# Teensy_FrequencyShield.net
KiCad netlist of a schematic drawn in EAGLE
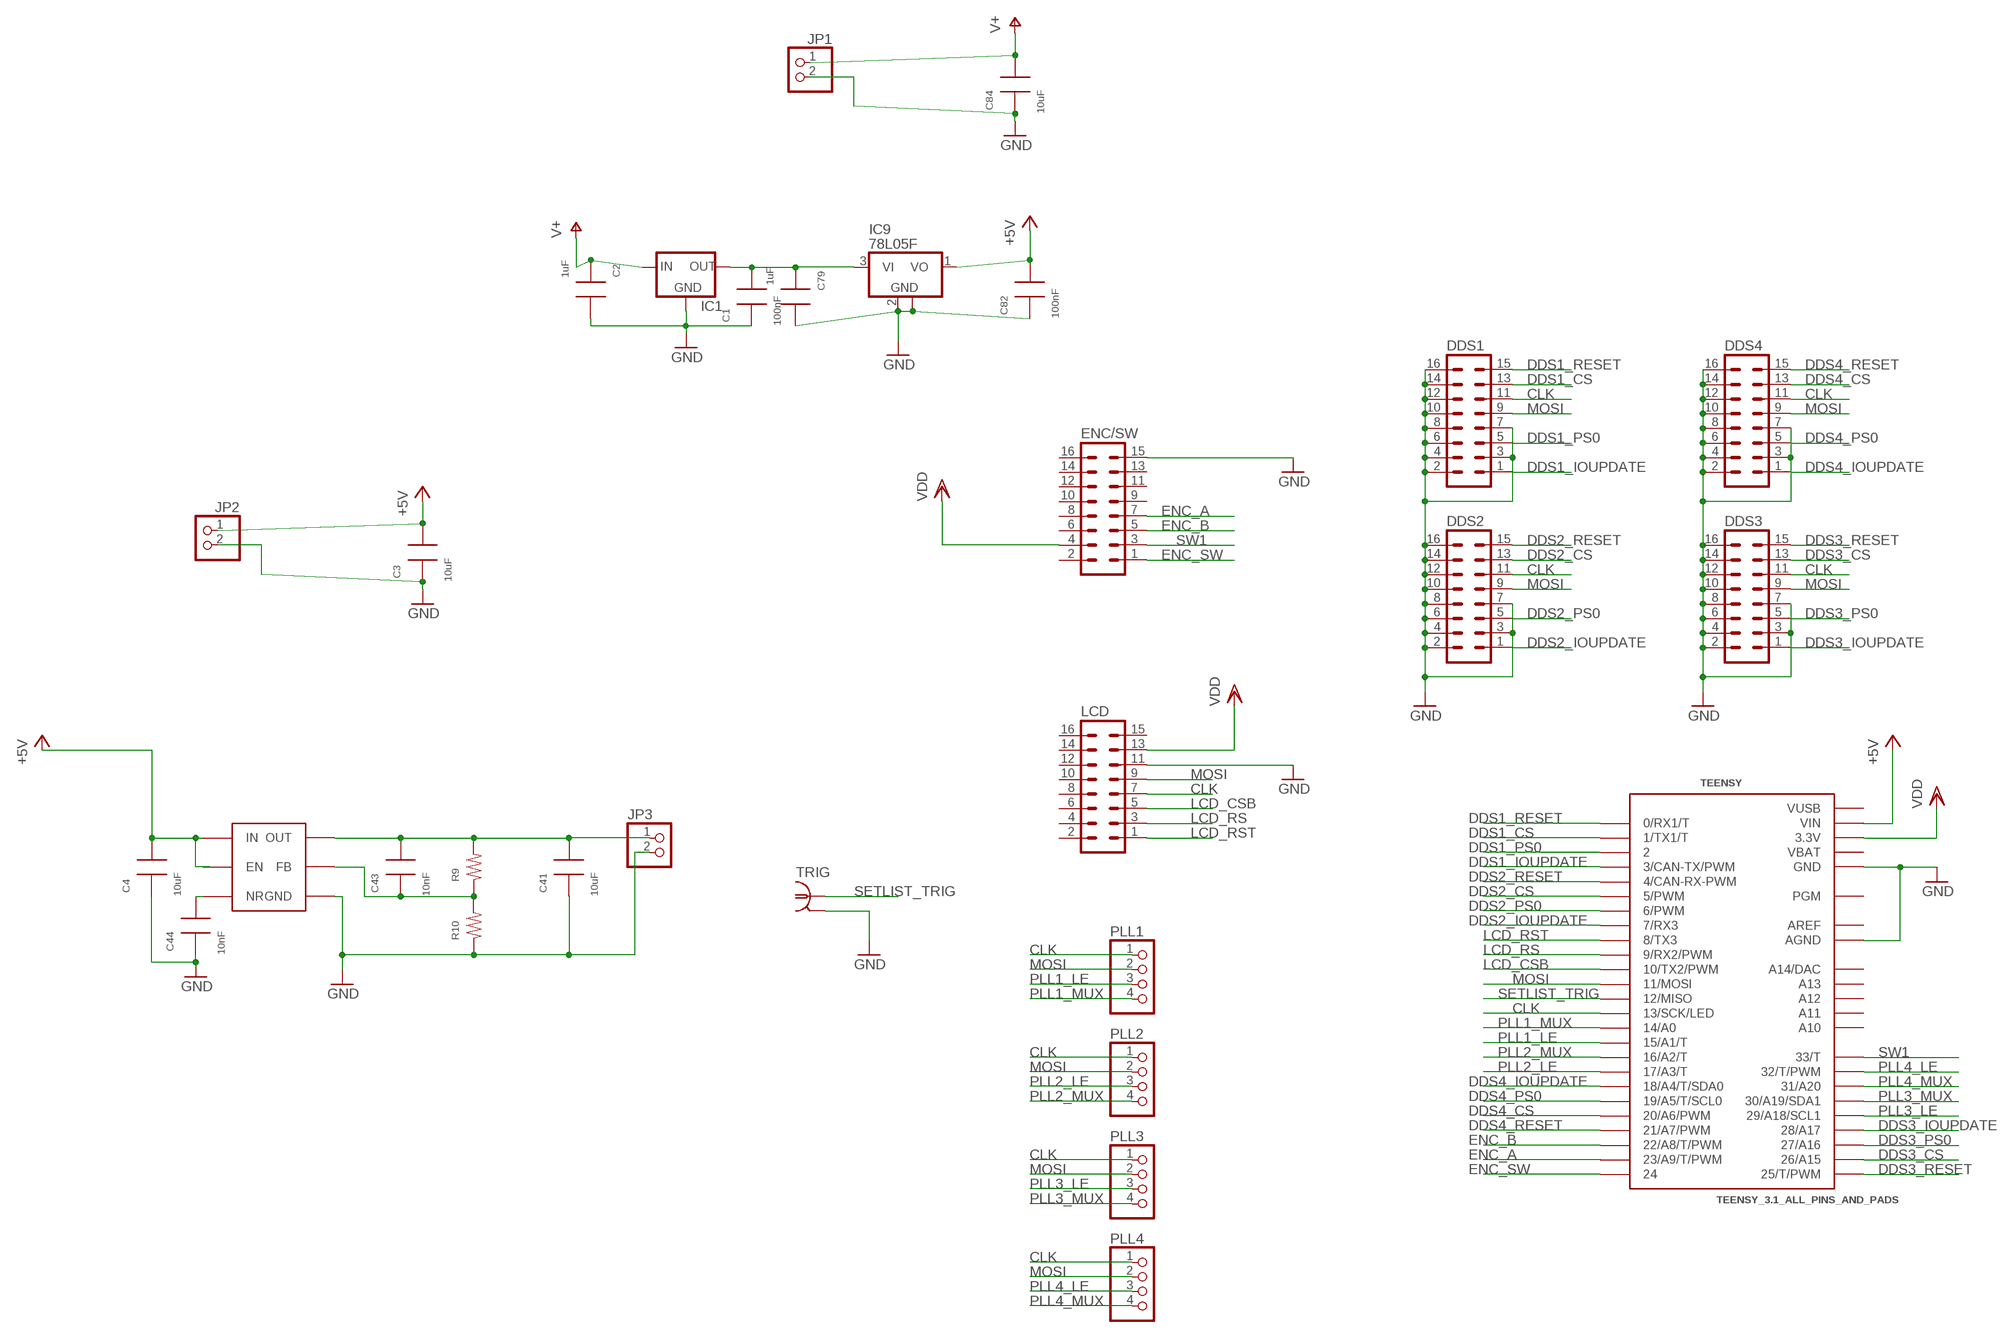
[diagram p0: schematic, sheet 1]

(export (version "E")
  (design (tool "Eeschema 10.0.6"))
  (components
    (comp (ref "C1")
      (value "100nF")
      (footprint "eagle-import:0603")
      (fields (field (name "PARTNO") "1276-1936-1-ND"))
      (libsource (lib "eagle-import") (part "CAP0603"))
    )
    (comp (ref "C2")
      (value "1uF")
      (footprint "eagle-import:0805")
      (fields (field (name "PARTNO") "1276-2396-1-ND"))
      (libsource (lib "eagle-import") (part "CAP0805"))
    )
    (comp (ref "C3")
      (value "10uF")
      (footprint "eagle-import:0805")
      (fields (field (name "PARTNO") "1276-2890-1-ND"))
      (libsource (lib "eagle-import") (part "CAP0805"))
    )
    (comp (ref "C4")
      (value "10uF")
      (footprint "eagle-import:0805")
      (fields (field (name "PARTNO") "1276-2890-1-ND"))
      (libsource (lib "eagle-import") (part "CAP0805"))
    )
    (comp (ref "C41")
      (value "10uF")
      (footprint "eagle-import:0805")
      (fields (field (name "PARTNO") "1276-2890-1-ND"))
      (libsource (lib "eagle-import") (part "CAP0805"))
    )
    (comp (ref "C43")
      (value "10nF")
      (footprint "eagle-import:0603")
      (fields (field (name "PARTNO") "1276-1921-1-ND"))
      (libsource (lib "eagle-import") (part "CAP0603"))
    )
    (comp (ref "C44")
      (value "10nF")
      (footprint "eagle-import:0603")
      (fields (field (name "PARTNO") "1276-1921-1-ND"))
      (libsource (lib "eagle-import") (part "CAP0603"))
    )
    (comp (ref "C79")
      (value "1uF")
      (footprint "eagle-import:0805")
      (fields (field (name "PARTNO") "1276-2396-1-ND"))
      (libsource (lib "eagle-import") (part "CAP0805"))
    )
    (comp (ref "C82")
      (value "100nF")
      (footprint "eagle-import:0603")
      (fields (field (name "PARTNO") "1276-1936-1-ND"))
      (libsource (lib "eagle-import") (part "CAP0603"))
    )
    (comp (ref "C84")
      (value "10uF")
      (footprint "eagle-import:0805")
      (fields (field (name "PARTNO") "1276-2890-1-ND"))
      (libsource (lib "eagle-import") (part "CAP0805"))
    )
    (comp (ref "DDS1")
      (value "ML16")
      (footprint "eagle-import:ML16")
      (libsource (lib "eagle-import") (part "ML16"))
    )
    (comp (ref "DDS2")
      (value "ML16")
      (footprint "eagle-import:ML16")
      (libsource (lib "eagle-import") (part "ML16"))
    )
    (comp (ref "DDS3")
      (value "ML16")
      (footprint "eagle-import:ML16")
      (libsource (lib "eagle-import") (part "ML16"))
    )
    (comp (ref "DDS4")
      (value "ML16")
      (footprint "eagle-import:ML16")
      (libsource (lib "eagle-import") (part "ML16"))
    )
    (comp (ref "ENC/SW")
      (value "ML16")
      (footprint "eagle-import:ML16")
      (libsource (lib "eagle-import") (part "ML16"))
    )
    (comp (ref "IC1")
      (value "78XX-TO220")
      (footprint "eagle-import:TO220")
      (libsource (lib "eagle-import") (part "78XX-TO220"))
    )
    (comp (ref "IC9")
      (value "78L05F")
      (footprint "eagle-import:SOT89")
      (fields (field (name "PARTNO") "MC78L05ACHXCT-ND"))
      (libsource (lib "eagle-import") (part "78LF05"))
    )
    (comp (ref "JP1")
      (value "PINHD-1X2")
      (footprint "eagle-import:1X02")
      (libsource (lib "eagle-import") (part "PINHD-1X2"))
    )
    (comp (ref "JP2")
      (value "PINHD-1X2")
      (footprint "eagle-import:1X02")
      (libsource (lib "eagle-import") (part "PINHD-1X2"))
    )
    (comp (ref "JP3")
      (value "PINHD-1X2")
      (footprint "eagle-import:1X02")
      (libsource (lib "eagle-import") (part "PINHD-1X2"))
    )
    (comp (ref "LCD")
      (value "ML16")
      (footprint "eagle-import:ML16")
      (fields (field (name "PARTNO") "S9171-ND"))
      (libsource (lib "eagle-import") (part "ML16"))
    )
    (comp (ref "PLL1")
      (value "PINHD-1X4")
      (footprint "eagle-import:1X04")
      (libsource (lib "eagle-import") (part "PINHD-1X4"))
    )
    (comp (ref "PLL2")
      (value "PINHD-1X4")
      (footprint "eagle-import:1X04")
      (libsource (lib "eagle-import") (part "PINHD-1X4"))
    )
    (comp (ref "PLL3")
      (value "PINHD-1X4")
      (footprint "eagle-import:1X04")
      (libsource (lib "eagle-import") (part "PINHD-1X4"))
    )
    (comp (ref "PLL4")
      (value "PINHD-1X4")
      (footprint "eagle-import:1X04")
      (libsource (lib "eagle-import") (part "PINHD-1X4"))
    )
    (comp (ref "R9")
      (value "RES0603")
      (footprint "eagle-import:0603")
      (fields (field (name "PARTNO") "P9.10KHCT-ND"))
      (libsource (lib "eagle-import") (part "RES0603"))
    )
    (comp (ref "R10")
      (value "RES0603")
      (footprint "eagle-import:0603")
      (fields (field (name "PARTNO") "P1.00KHCT-ND"))
      (libsource (lib "eagle-import") (part "RES0603"))
    )
    (comp (ref "TEENSY")
      (value "TEENSY_3.1_ALL_PINS_AND_PADS")
      (footprint "eagle-import:TEENSY_3.1_ALLPINS")
      (libsource (lib "eagle-import") (part "TEENSY_3.1_ALL_PINS_AND_PADS"))
    )
    (comp (ref "TRIG")
      (value "BNC-H")
      (footprint "eagle-import:BNC90")
      (libsource (lib "eagle-import") (part "BNC-H"))
    )
    (comp (ref "U4")
      (value "TPS7A4901")
      (footprint "eagle-import:DGN")
      (fields (field (name "PARTNO") "296-27751-1-ND"))
      (libsource (lib "eagle-import") (part "TPS7A49XX"))
    )
  )
  (nets
    (net (code "1") (name "+5V") (class "Default")
      (node (ref "C3") (pin "2") (pinfunction "P$2_2") (pintype "passive"))
      (node (ref "C4") (pin "2") (pinfunction "P$2_2") (pintype "passive"))
      (node (ref "C82") (pin "2") (pinfunction "P$2_2") (pintype "passive"))
      (node (ref "IC9") (pin "1") (pinfunction "VO_1") (pintype "passive"))
      (node (ref "JP2") (pin "1") (pinfunction "1_1") (pintype "passive"))
      (node (ref "TEENSY") (pin "VIN") (pinfunction "VIN_VIN") (pintype "power_in"))
      (node (ref "U4") (pin "IN") (pinfunction "IN_IN") (pintype "bidirectional"))
    )
    (net (code "2") (name "/AREF") (class "Default")
      (node (ref "TEENSY") (pin "AREF") (pinfunction "AREF_AREF") (pintype "power_in"))
    )
    (net (code "3") (name "/CLK") (class "Default")
      (node (ref "DDS1") (pin "11") (pinfunction "11_11") (pintype "passive"))
      (node (ref "DDS2") (pin "11") (pinfunction "11_11") (pintype "passive"))
      (node (ref "DDS3") (pin "11") (pinfunction "11_11") (pintype "passive"))
      (node (ref "DDS4") (pin "11") (pinfunction "11_11") (pintype "passive"))
      (node (ref "LCD") (pin "7") (pinfunction "7_7") (pintype "passive"))
      (node (ref "PLL1") (pin "1") (pinfunction "1_1") (pintype "passive"))
      (node (ref "PLL2") (pin "1") (pinfunction "1_1") (pintype "passive"))
      (node (ref "PLL3") (pin "1") (pinfunction "1_1") (pintype "passive"))
      (node (ref "PLL4") (pin "1") (pinfunction "1_1") (pintype "passive"))
      (node (ref "TEENSY") (pin "13") (pinfunction "13/SCK/LED_13") (pintype "bidirectional"))
    )
    (net (code "4") (name "/DDS1_CS") (class "Default")
      (node (ref "DDS1") (pin "13") (pinfunction "13_13") (pintype "passive"))
      (node (ref "TEENSY") (pin "1") (pinfunction "1/TX1/T_1") (pintype "bidirectional"))
    )
    (net (code "5") (name "/DDS1_IOUPDATE") (class "Default")
      (node (ref "DDS1") (pin "1") (pinfunction "1_1") (pintype "passive"))
      (node (ref "TEENSY") (pin "3") (pinfunction "3/CAN-TX/PWM_3") (pintype "bidirectional"))
    )
    (net (code "6") (name "/DDS1_PS0") (class "Default")
      (node (ref "DDS1") (pin "5") (pinfunction "5_5") (pintype "passive"))
      (node (ref "TEENSY") (pin "2") (pinfunction "2_2") (pintype "bidirectional"))
    )
    (net (code "7") (name "/DDS1_RESET") (class "Default")
      (node (ref "DDS1") (pin "15") (pinfunction "15_15") (pintype "passive"))
      (node (ref "TEENSY") (pin "0") (pinfunction "0/RX1/T_0") (pintype "bidirectional"))
    )
    (net (code "8") (name "/DDS2_CS") (class "Default")
      (node (ref "DDS2") (pin "13") (pinfunction "13_13") (pintype "passive"))
      (node (ref "TEENSY") (pin "5") (pinfunction "5/PWM_5") (pintype "bidirectional"))
    )
    (net (code "9") (name "/DDS2_IOUPDATE") (class "Default")
      (node (ref "DDS2") (pin "1") (pinfunction "1_1") (pintype "passive"))
      (node (ref "TEENSY") (pin "7") (pinfunction "7/RX3_7") (pintype "bidirectional"))
    )
    (net (code "10") (name "/DDS2_PS0") (class "Default")
      (node (ref "DDS2") (pin "5") (pinfunction "5_5") (pintype "passive"))
      (node (ref "TEENSY") (pin "6") (pinfunction "6/PWM_6") (pintype "bidirectional"))
    )
    (net (code "11") (name "/DDS2_RESET") (class "Default")
      (node (ref "DDS2") (pin "15") (pinfunction "15_15") (pintype "passive"))
      (node (ref "TEENSY") (pin "4") (pinfunction "4/CAN-RX-PWM_4") (pintype "bidirectional"))
    )
    (net (code "12") (name "/DDS3_CS") (class "Default")
      (node (ref "DDS3") (pin "13") (pinfunction "13_13") (pintype "passive"))
      (node (ref "TEENSY") (pin "26") (pinfunction "26/A15_26") (pintype "bidirectional"))
    )
    (net (code "13") (name "/DDS3_IOUPDATE") (class "Default")
      (node (ref "DDS3") (pin "1") (pinfunction "1_1") (pintype "passive"))
      (node (ref "TEENSY") (pin "28") (pinfunction "28/A17_28") (pintype "bidirectional"))
    )
    (net (code "14") (name "/DDS3_PS0") (class "Default")
      (node (ref "DDS3") (pin "5") (pinfunction "5_5") (pintype "passive"))
      (node (ref "TEENSY") (pin "27") (pinfunction "27/A16_27") (pintype "bidirectional"))
    )
    (net (code "15") (name "/DDS3_RESET") (class "Default")
      (node (ref "DDS3") (pin "15") (pinfunction "15_15") (pintype "passive"))
      (node (ref "TEENSY") (pin "25") (pinfunction "25/T/PWM_25") (pintype "bidirectional"))
    )
    (net (code "16") (name "/DDS4_CS") (class "Default")
      (node (ref "DDS4") (pin "13") (pinfunction "13_13") (pintype "passive"))
      (node (ref "TEENSY") (pin "20/A6") (pinfunction "20/A6/PWM_20/A6") (pintype "bidirectional"))
    )
    (net (code "17") (name "/DDS4_IOUPDATE") (class "Default")
      (node (ref "DDS4") (pin "1") (pinfunction "1_1") (pintype "passive"))
      (node (ref "TEENSY") (pin "18/A4") (pinfunction "18/A4/T/SDA0_18/A4") (pintype "bidirectional"))
    )
    (net (code "18") (name "/DDS4_PS0") (class "Default")
      (node (ref "DDS4") (pin "5") (pinfunction "5_5") (pintype "passive"))
      (node (ref "TEENSY") (pin "19/A5") (pinfunction "19/A5/T/SCL0_19/A5") (pintype "bidirectional"))
    )
    (net (code "19") (name "/DDS4_RESET") (class "Default")
      (node (ref "DDS4") (pin "15") (pinfunction "15_15") (pintype "passive"))
      (node (ref "TEENSY") (pin "21/A7") (pinfunction "21/A7/PWM_21/A7") (pintype "bidirectional"))
    )
    (net (code "20") (name "/ENC_A") (class "Default")
      (node (ref "ENC/SW") (pin "7") (pinfunction "7_7") (pintype "passive"))
      (node (ref "TEENSY") (pin "23/A9") (pinfunction "23/A9/T/PWM_23/A9") (pintype "bidirectional"))
    )
    (net (code "21") (name "/ENC_B") (class "Default")
      (node (ref "ENC/SW") (pin "5") (pinfunction "5_5") (pintype "passive"))
      (node (ref "TEENSY") (pin "22/A8") (pinfunction "22/A8/T/PWM_22/A8") (pintype "bidirectional"))
    )
    (net (code "22") (name "/ENC_SW") (class "Default")
      (node (ref "ENC/SW") (pin "1") (pinfunction "1_1") (pintype "passive"))
      (node (ref "TEENSY") (pin "24") (pinfunction "24_24") (pintype "bidirectional"))
    )
    (net (code "23") (name "/LCD_CSB") (class "Default")
      (node (ref "LCD") (pin "5") (pinfunction "5_5") (pintype "passive"))
      (node (ref "TEENSY") (pin "10") (pinfunction "10/TX2/PWM_10") (pintype "bidirectional"))
    )
    (net (code "24") (name "/LCD_RS") (class "Default")
      (node (ref "LCD") (pin "3") (pinfunction "3_3") (pintype "passive"))
      (node (ref "TEENSY") (pin "9") (pinfunction "9/RX2/PWM_9") (pintype "bidirectional"))
    )
    (net (code "25") (name "/LCD_RST") (class "Default")
      (node (ref "LCD") (pin "1") (pinfunction "1_1") (pintype "passive"))
      (node (ref "TEENSY") (pin "8") (pinfunction "8/TX3_8") (pintype "bidirectional"))
    )
    (net (code "26") (name "/MOSI") (class "Default")
      (node (ref "DDS1") (pin "9") (pinfunction "9_9") (pintype "passive"))
      (node (ref "DDS2") (pin "9") (pinfunction "9_9") (pintype "passive"))
      (node (ref "DDS3") (pin "9") (pinfunction "9_9") (pintype "passive"))
      (node (ref "DDS4") (pin "9") (pinfunction "9_9") (pintype "passive"))
      (node (ref "LCD") (pin "9") (pinfunction "9_9") (pintype "passive"))
      (node (ref "PLL1") (pin "2") (pinfunction "2_2") (pintype "passive"))
      (node (ref "PLL2") (pin "2") (pinfunction "2_2") (pintype "passive"))
      (node (ref "PLL3") (pin "2") (pinfunction "2_2") (pintype "passive"))
      (node (ref "PLL4") (pin "2") (pinfunction "2_2") (pintype "passive"))
      (node (ref "TEENSY") (pin "11") (pinfunction "11/MOSI_11") (pintype "bidirectional"))
    )
    (net (code "27") (name "/PLL1_LE") (class "Default")
      (node (ref "PLL1") (pin "3") (pinfunction "3_3") (pintype "passive"))
      (node (ref "TEENSY") (pin "15/A1") (pinfunction "15/A1/T_15/A1") (pintype "bidirectional"))
    )
    (net (code "28") (name "/PLL1_MUX") (class "Default")
      (node (ref "PLL1") (pin "4") (pinfunction "4_4") (pintype "passive"))
      (node (ref "TEENSY") (pin "14/A0") (pinfunction "14/A0_14/A0") (pintype "bidirectional"))
    )
    (net (code "29") (name "/PLL2_LE") (class "Default")
      (node (ref "PLL2") (pin "3") (pinfunction "3_3") (pintype "passive"))
      (node (ref "TEENSY") (pin "17/A3") (pinfunction "17/A3/T_17/A3") (pintype "bidirectional"))
    )
    (net (code "30") (name "/PLL2_MUX") (class "Default")
      (node (ref "PLL2") (pin "4") (pinfunction "4_4") (pintype "passive"))
      (node (ref "TEENSY") (pin "16/A2") (pinfunction "16/A2/T_16/A2") (pintype "bidirectional"))
    )
    (net (code "31") (name "/PLL3_LE") (class "Default")
      (node (ref "PLL3") (pin "3") (pinfunction "3_3") (pintype "passive"))
      (node (ref "TEENSY") (pin "29") (pinfunction "29/A18/SCL1_29") (pintype "bidirectional"))
    )
    (net (code "32") (name "/PLL3_MUX") (class "Default")
      (node (ref "PLL3") (pin "4") (pinfunction "4_4") (pintype "passive"))
      (node (ref "TEENSY") (pin "30") (pinfunction "30/A19/SDA1_30") (pintype "bidirectional"))
    )
    (net (code "33") (name "/PLL4_LE") (class "Default")
      (node (ref "PLL4") (pin "3") (pinfunction "3_3") (pintype "passive"))
      (node (ref "TEENSY") (pin "32") (pinfunction "32/T/PWM_32") (pintype "bidirectional"))
    )
    (net (code "34") (name "/PLL4_MUX") (class "Default")
      (node (ref "PLL4") (pin "4") (pinfunction "4_4") (pintype "passive"))
      (node (ref "TEENSY") (pin "31") (pinfunction "31/A20_31") (pintype "bidirectional"))
    )
    (net (code "35") (name "/SETLIST_TRIG") (class "Default")
      (node (ref "TEENSY") (pin "12") (pinfunction "12/MISO_12") (pintype "bidirectional"))
      (node (ref "TRIG") (pin "1") (pinfunction "1_1") (pintype "passive"))
    )
    (net (code "36") (name "/SW1") (class "Default")
      (node (ref "ENC/SW") (pin "3") (pinfunction "3_3") (pintype "passive"))
      (node (ref "TEENSY") (pin "33") (pinfunction "33/T_33") (pintype "bidirectional"))
    )
    (net (code "37") (name "/VBAT") (class "Default")
      (node (ref "TEENSY") (pin "VBAT") (pinfunction "VBAT_VBAT") (pintype "power_in"))
    )
    (net (code "38") (name "/VUSB") (class "Default")
      (node (ref "TEENSY") (pin "VUSB") (pinfunction "VUSB_VUSB") (pintype "power_in"))
    )
    (net (code "39") (name "GND") (class "Default")
      (node (ref "C1") (pin "1") (pinfunction "P$1_1") (pintype "passive"))
      (node (ref "C2") (pin "2") (pinfunction "P$2_2") (pintype "passive"))
      (node (ref "C3") (pin "1") (pinfunction "P$1_1") (pintype "passive"))
      (node (ref "C4") (pin "1") (pinfunction "P$1_1") (pintype "passive"))
      (node (ref "C41") (pin "1") (pinfunction "P$1_1") (pintype "passive"))
      (node (ref "C44") (pin "1") (pinfunction "P$1_1") (pintype "passive"))
      (node (ref "C79") (pin "2") (pinfunction "P$2_2") (pintype "passive"))
      (node (ref "C82") (pin "1") (pinfunction "P$1_1") (pintype "passive"))
      (node (ref "C84") (pin "1") (pinfunction "P$1_1") (pintype "passive"))
      (node (ref "DDS1") (pin "10") (pinfunction "10_10") (pintype "passive"))
      (node (ref "DDS1") (pin "12") (pinfunction "12_12") (pintype "passive"))
      (node (ref "DDS1") (pin "14") (pinfunction "14_14") (pintype "passive"))
      (node (ref "DDS1") (pin "16") (pinfunction "16_16") (pintype "passive"))
      (node (ref "DDS1") (pin "2") (pinfunction "2_2") (pintype "passive"))
      (node (ref "DDS1") (pin "3") (pinfunction "3_3") (pintype "passive"))
      (node (ref "DDS1") (pin "4") (pinfunction "4_4") (pintype "passive"))
      (node (ref "DDS1") (pin "6") (pinfunction "6_6") (pintype "passive"))
      (node (ref "DDS1") (pin "7") (pinfunction "7_7") (pintype "passive"))
      (node (ref "DDS1") (pin "8") (pinfunction "8_8") (pintype "passive"))
      (node (ref "DDS2") (pin "10") (pinfunction "10_10") (pintype "passive"))
      (node (ref "DDS2") (pin "12") (pinfunction "12_12") (pintype "passive"))
      (node (ref "DDS2") (pin "14") (pinfunction "14_14") (pintype "passive"))
      (node (ref "DDS2") (pin "16") (pinfunction "16_16") (pintype "passive"))
      (node (ref "DDS2") (pin "2") (pinfunction "2_2") (pintype "passive"))
      (node (ref "DDS2") (pin "3") (pinfunction "3_3") (pintype "passive"))
      (node (ref "DDS2") (pin "4") (pinfunction "4_4") (pintype "passive"))
      (node (ref "DDS2") (pin "6") (pinfunction "6_6") (pintype "passive"))
      (node (ref "DDS2") (pin "7") (pinfunction "7_7") (pintype "passive"))
      (node (ref "DDS2") (pin "8") (pinfunction "8_8") (pintype "passive"))
      (node (ref "DDS3") (pin "10") (pinfunction "10_10") (pintype "passive"))
      (node (ref "DDS3") (pin "12") (pinfunction "12_12") (pintype "passive"))
      (node (ref "DDS3") (pin "14") (pinfunction "14_14") (pintype "passive"))
      (node (ref "DDS3") (pin "16") (pinfunction "16_16") (pintype "passive"))
      (node (ref "DDS3") (pin "2") (pinfunction "2_2") (pintype "passive"))
      (node (ref "DDS3") (pin "3") (pinfunction "3_3") (pintype "passive"))
      (node (ref "DDS3") (pin "4") (pinfunction "4_4") (pintype "passive"))
      (node (ref "DDS3") (pin "6") (pinfunction "6_6") (pintype "passive"))
      (node (ref "DDS3") (pin "7") (pinfunction "7_7") (pintype "passive"))
      (node (ref "DDS3") (pin "8") (pinfunction "8_8") (pintype "passive"))
      (node (ref "DDS4") (pin "10") (pinfunction "10_10") (pintype "passive"))
      (node (ref "DDS4") (pin "12") (pinfunction "12_12") (pintype "passive"))
      (node (ref "DDS4") (pin "14") (pinfunction "14_14") (pintype "passive"))
      (node (ref "DDS4") (pin "16") (pinfunction "16_16") (pintype "passive"))
      (node (ref "DDS4") (pin "2") (pinfunction "2_2") (pintype "passive"))
      (node (ref "DDS4") (pin "3") (pinfunction "3_3") (pintype "passive"))
      (node (ref "DDS4") (pin "4") (pinfunction "4_4") (pintype "passive"))
      (node (ref "DDS4") (pin "6") (pinfunction "6_6") (pintype "passive"))
      (node (ref "DDS4") (pin "7") (pinfunction "7_7") (pintype "passive"))
      (node (ref "DDS4") (pin "8") (pinfunction "8_8") (pintype "passive"))
      (node (ref "ENC/SW") (pin "15") (pinfunction "15_15") (pintype "passive"))
      (node (ref "IC1") (pin "2") (pinfunction "GND_2") (pintype "input"))
      (node (ref "IC9") (pin "2") (pinfunction "GND_2") (pintype "passive"))
      (node (ref "IC9") (pin "2@1") (pinfunction "GND_2@1") (pintype "passive"))
      (node (ref "JP1") (pin "2") (pinfunction "2_2") (pintype "passive"))
      (node (ref "JP2") (pin "2") (pinfunction "2_2") (pintype "passive"))
      (node (ref "JP3") (pin "2") (pinfunction "2_2") (pintype "passive"))
      (node (ref "LCD") (pin "11") (pinfunction "11_11") (pintype "passive"))
      (node (ref "R10") (pin "1") (pinfunction "P$1_1") (pintype "passive"))
      (node (ref "TEENSY") (pin "AGND") (pinfunction "AGND_AGND") (pintype "power_in"))
      (node (ref "TEENSY") (pin "GND") (pinfunction "GND_GND") (pintype "power_in"))
      (node (ref "TEENSY") (pin "GND1") (pinfunction "GND_GND1") (pintype "power_in"))
      (node (ref "TEENSY") (pin "GND2") (pinfunction "GND_GND2") (pintype "power_in"))
      (node (ref "TRIG") (pin "2") (pinfunction "2_2") (pintype "passive"))
      (node (ref "U4") (pin "GND") (pinfunction "GND_GND") (pintype "bidirectional"))
      (node (ref "U4") (pin "GND1") (pinfunction "GND_GND1") (pintype "bidirectional"))
    )
    (net (code "40") (name "Net-(C1-P$2)") (class "Default")
      (node (ref "C1") (pin "2") (pinfunction "P$2_2") (pintype "passive"))
      (node (ref "C79") (pin "1") (pinfunction "P$1_1") (pintype "passive"))
      (node (ref "IC1") (pin "3") (pinfunction "OUT_3") (pintype "passive"))
      (node (ref "IC9") (pin "3") (pinfunction "VI_3") (pintype "input"))
    )
    (net (code "41") (name "Net-(C41-P$2)") (class "Default")
      (node (ref "C41") (pin "2") (pinfunction "P$2_2") (pintype "passive"))
      (node (ref "C43") (pin "2") (pinfunction "P$2_2") (pintype "passive"))
      (node (ref "JP3") (pin "1") (pinfunction "1_1") (pintype "passive"))
      (node (ref "R9") (pin "2") (pinfunction "P$2_2") (pintype "passive"))
      (node (ref "U4") (pin "OUT") (pinfunction "OUT_OUT") (pintype "bidirectional"))
    )
    (net (code "42") (name "Net-(C43-P$1)") (class "Default")
      (node (ref "C43") (pin "1") (pinfunction "P$1_1") (pintype "passive"))
      (node (ref "R10") (pin "2") (pinfunction "P$2_2") (pintype "passive"))
      (node (ref "R9") (pin "1") (pinfunction "P$1_1") (pintype "passive"))
      (node (ref "U4") (pin "FB") (pinfunction "FB_FB") (pintype "bidirectional"))
    )
    (net (code "43") (name "Net-(C44-P$2)") (class "Default")
      (node (ref "C44") (pin "2") (pinfunction "P$2_2") (pintype "passive"))
      (node (ref "U4") (pin "NR/SS") (pinfunction "NR_NR/SS") (pintype "bidirectional"))
    )
    (net (code "44") (name "V+") (class "Default")
      (node (ref "C2") (pin "1") (pinfunction "P$1_1") (pintype "passive"))
      (node (ref "C84") (pin "2") (pinfunction "P$2_2") (pintype "passive"))
      (node (ref "IC1") (pin "1") (pinfunction "IN_1") (pintype "input"))
      (node (ref "JP1") (pin "1") (pinfunction "1_1") (pintype "passive"))
    )
    (net (code "45") (name "VDD") (class "Default")
      (node (ref "ENC/SW") (pin "4") (pinfunction "4_4") (pintype "passive"))
      (node (ref "LCD") (pin "13") (pinfunction "13_13") (pintype "passive"))
      (node (ref "TEENSY") (pin "3.3V") (pinfunction "3.3V_3.3V") (pintype "power_in"))
      (node (ref "TEENSY") (pin "3.3V1") (pinfunction "3.3V_3.3V1") (pintype "power_in"))
      (node (ref "TEENSY") (pin "3.3V2") (pinfunction "3.3V_3.3V2") (pintype "power_in"))
    )
    (net (code "46") (name "unconnected-(ENC/SW-Pad2)") (class "Default")
      (node (ref "ENC/SW") (pin "2") (pinfunction "2_2") (pintype "passive"))
    )
    (net (code "47") (name "unconnected-(ENC/SW-Pad6)") (class "Default")
      (node (ref "ENC/SW") (pin "6") (pinfunction "6_6") (pintype "passive"))
    )
    (net (code "48") (name "unconnected-(ENC/SW-Pad8)") (class "Default")
      (node (ref "ENC/SW") (pin "8") (pinfunction "8_8") (pintype "passive"))
    )
    (net (code "49") (name "unconnected-(ENC/SW-Pad9)") (class "Default")
      (node (ref "ENC/SW") (pin "9") (pinfunction "9_9") (pintype "passive"))
    )
    (net (code "50") (name "unconnected-(ENC/SW-Pad10)") (class "Default")
      (node (ref "ENC/SW") (pin "10") (pinfunction "10_10") (pintype "passive"))
    )
    (net (code "51") (name "unconnected-(ENC/SW-Pad11)") (class "Default")
      (node (ref "ENC/SW") (pin "11") (pinfunction "11_11") (pintype "passive"))
    )
    (net (code "52") (name "unconnected-(ENC/SW-Pad12)") (class "Default")
      (node (ref "ENC/SW") (pin "12") (pinfunction "12_12") (pintype "passive"))
    )
    (net (code "53") (name "unconnected-(ENC/SW-Pad13)") (class "Default")
      (node (ref "ENC/SW") (pin "13") (pinfunction "13_13") (pintype "passive"))
    )
    (net (code "54") (name "unconnected-(ENC/SW-Pad14)") (class "Default")
      (node (ref "ENC/SW") (pin "14") (pinfunction "14_14") (pintype "passive"))
    )
    (net (code "55") (name "unconnected-(ENC/SW-Pad16)") (class "Default")
      (node (ref "ENC/SW") (pin "16") (pinfunction "16_16") (pintype "passive"))
    )
    (net (code "56") (name "unconnected-(LCD-Pad2)") (class "Default")
      (node (ref "LCD") (pin "2") (pinfunction "2_2") (pintype "passive"))
    )
    (net (code "57") (name "unconnected-(LCD-Pad4)") (class "Default")
      (node (ref "LCD") (pin "4") (pinfunction "4_4") (pintype "passive"))
    )
    (net (code "58") (name "unconnected-(LCD-Pad6)") (class "Default")
      (node (ref "LCD") (pin "6") (pinfunction "6_6") (pintype "passive"))
    )
    (net (code "59") (name "unconnected-(LCD-Pad8)") (class "Default")
      (node (ref "LCD") (pin "8") (pinfunction "8_8") (pintype "passive"))
    )
    (net (code "60") (name "unconnected-(LCD-Pad10)") (class "Default")
      (node (ref "LCD") (pin "10") (pinfunction "10_10") (pintype "passive"))
    )
    (net (code "61") (name "unconnected-(LCD-Pad12)") (class "Default")
      (node (ref "LCD") (pin "12") (pinfunction "12_12") (pintype "passive"))
    )
    (net (code "62") (name "unconnected-(LCD-Pad14)") (class "Default")
      (node (ref "LCD") (pin "14") (pinfunction "14_14") (pintype "passive"))
    )
    (net (code "63") (name "unconnected-(LCD-Pad15)") (class "Default")
      (node (ref "LCD") (pin "15") (pinfunction "15_15") (pintype "passive"))
    )
    (net (code "64") (name "unconnected-(LCD-Pad16)") (class "Default")
      (node (ref "LCD") (pin "16") (pinfunction "16_16") (pintype "passive"))
    )
    (net (code "65") (name "unconnected-(TEENSY-A14{slash}DAC-PadA14)") (class "Default")
      (node (ref "TEENSY") (pin "A14") (pinfunction "A14/DAC_A14") (pintype "bidirectional"))
    )
    (net (code "66") (name "unconnected-(TEENSY-PadA10)") (class "Default")
      (node (ref "TEENSY") (pin "A10") (pinfunction "A10_A10") (pintype "bidirectional"))
    )
    (net (code "67") (name "unconnected-(TEENSY-PadA11)") (class "Default")
      (node (ref "TEENSY") (pin "A11") (pinfunction "A11_A11") (pintype "bidirectional"))
    )
    (net (code "68") (name "unconnected-(TEENSY-PadA12)") (class "Default")
      (node (ref "TEENSY") (pin "A12") (pinfunction "A12_A12") (pintype "bidirectional"))
    )
    (net (code "69") (name "unconnected-(TEENSY-PadA13)") (class "Default")
      (node (ref "TEENSY") (pin "A13") (pinfunction "A13_A13") (pintype "bidirectional"))
    )
    (net (code "70") (name "unconnected-(TEENSY-PadPGM)") (class "Default")
      (node (ref "TEENSY") (pin "PGM") (pinfunction "PGM_PGM") (pintype "bidirectional"))
    )
    (net (code "71") (name "unconnected-(U4-PadEN)") (class "Default")
      (node (ref "U4") (pin "EN") (pinfunction "EN_EN") (pintype "bidirectional"))
    )
  )
)
